# Measurements.net
KiCad netlist of a schematic drawn in Altium Designer
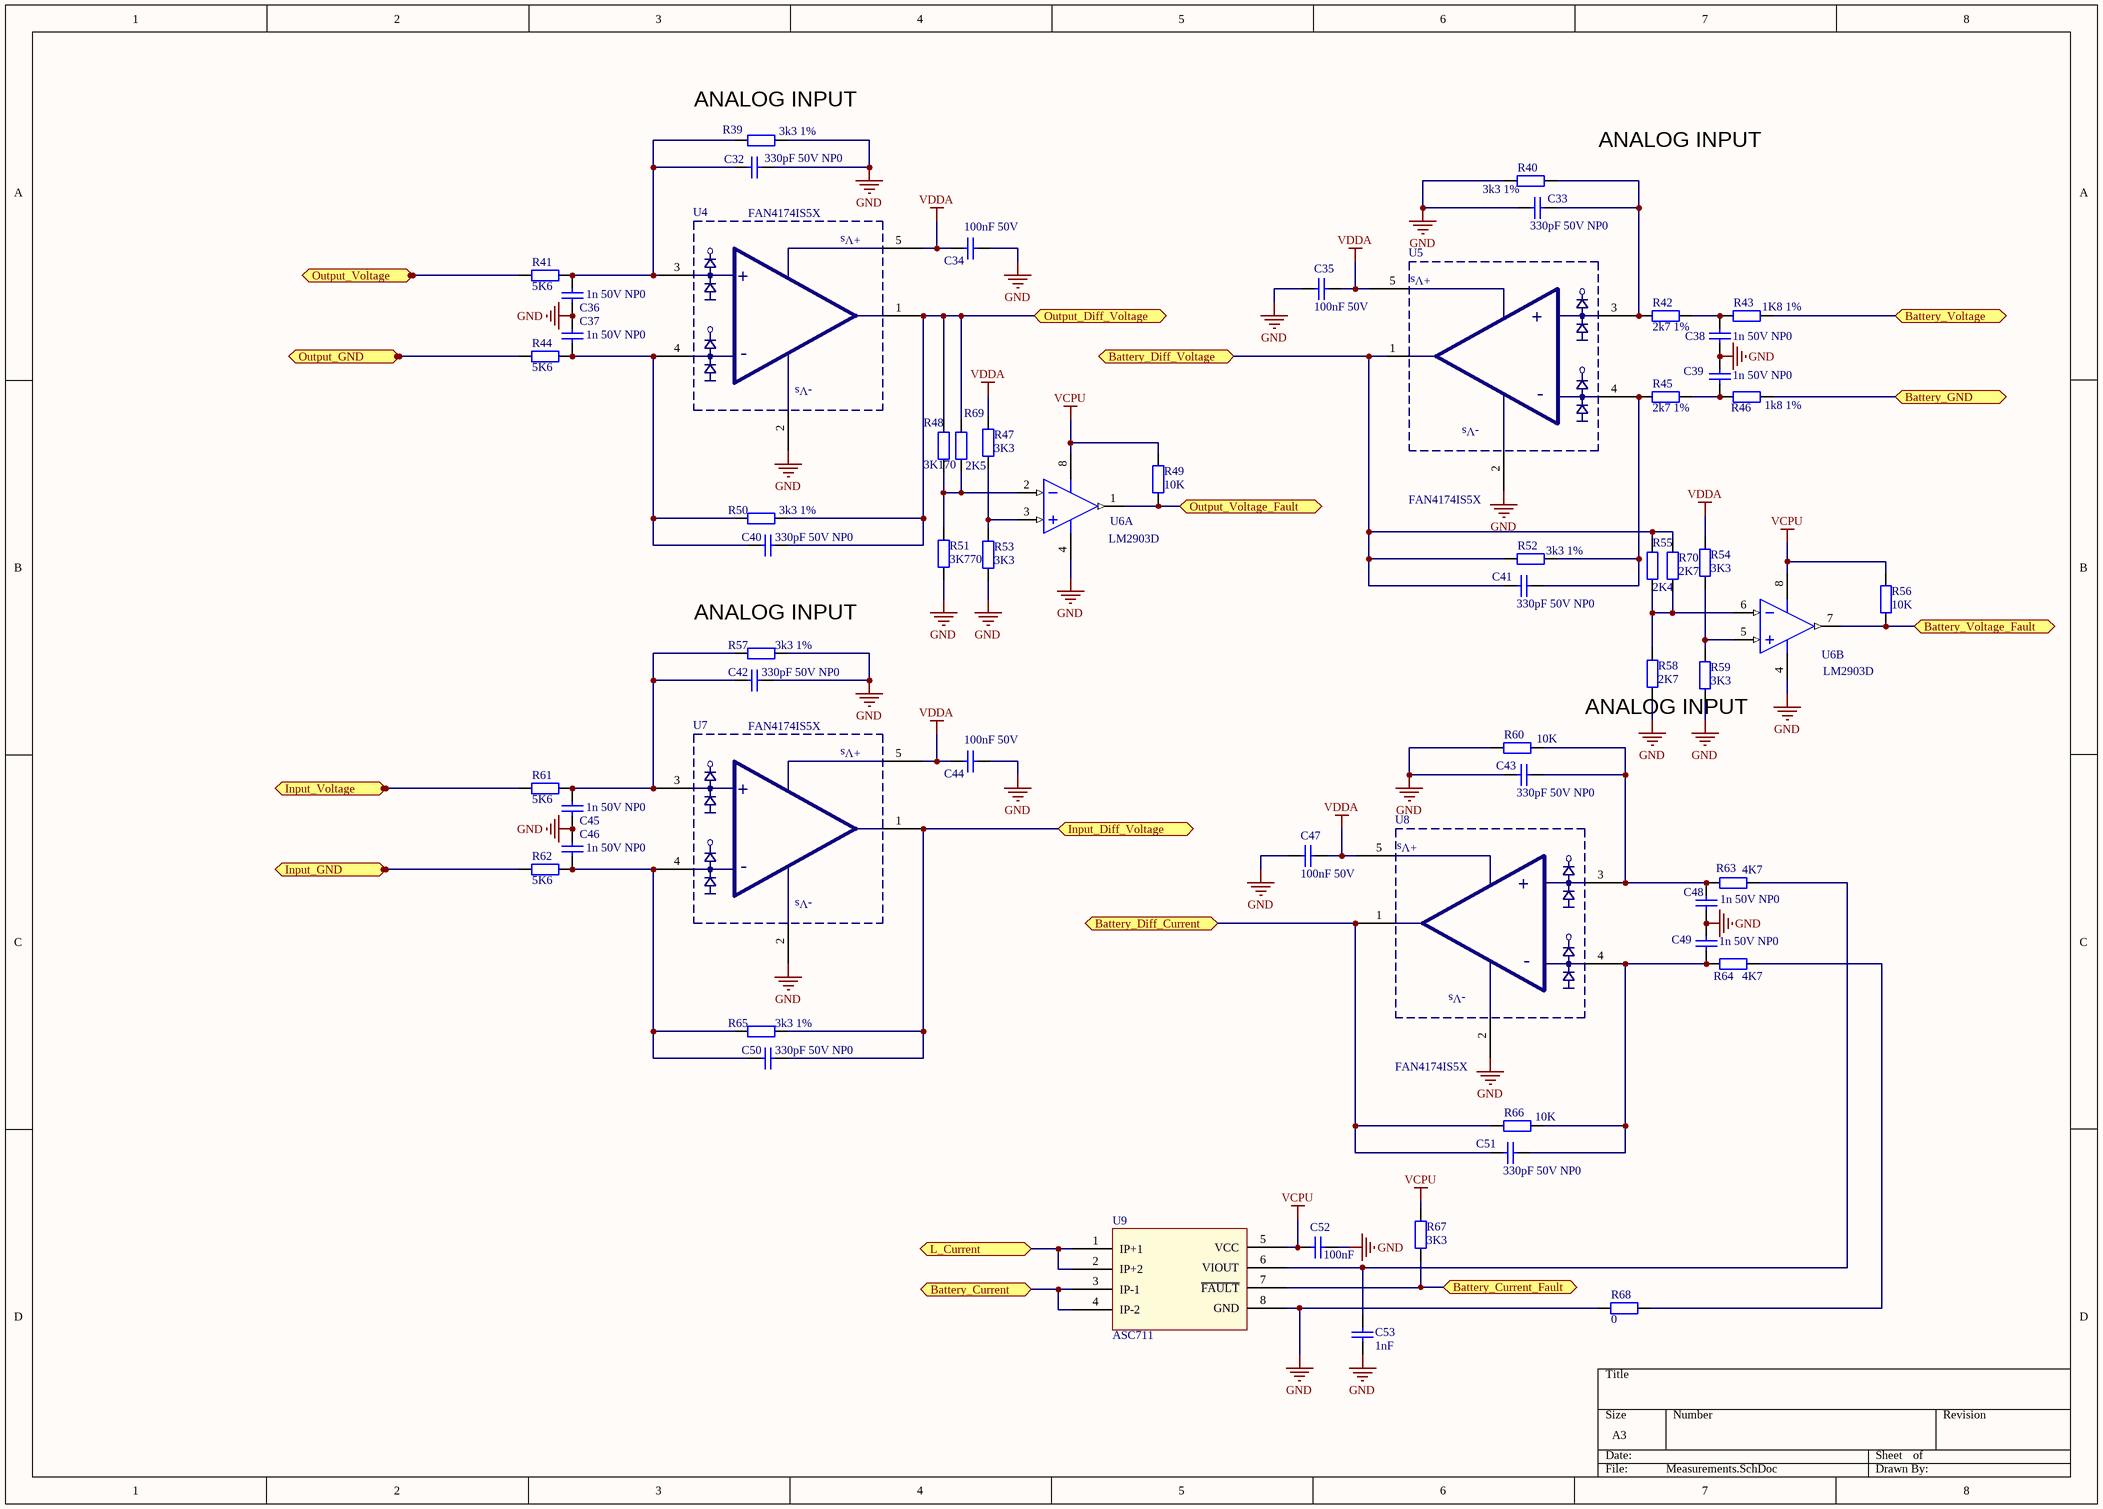
[diagram p0: Measurements.SchDoc]

(export (version "E")
  (design (tool "Eeschema 10.0.6"))
  (components
    (comp (ref "C32")
      (value "330pF 50V NP0")
      (footprint "0805_C")
      (description "SMD kondenzátorok")
      (libsource (lib "MERES") (part "Capacitor_SMD"))
    )
    (comp (ref "C33")
      (value "330pF 50V NP0")
      (footprint "0805_C")
      (description "SMD kondenzátorok")
      (libsource (lib "MERES") (part "Capacitor_SMD"))
    )
    (comp (ref "C34")
      (value "100nF 50V")
      (footprint "0805_C")
      (description "SMD kondenzátorok")
      (libsource (lib "MERES") (part "Capacitor_SMD"))
    )
    (comp (ref "C35")
      (value "100nF 50V")
      (footprint "0805_C")
      (description "SMD kondenzátorok")
      (libsource (lib "MERES") (part "Capacitor_SMD"))
    )
    (comp (ref "C36")
      (value "1n 50V NP0")
      (footprint "FP_0805_CAP_085")
      (libsource (lib "MERES") (part "Capacitor_SMD"))
    )
    (comp (ref "C37")
      (value "1n 50V NP0")
      (footprint "FP_0805_CAP_085")
      (libsource (lib "MERES") (part "Capacitor_SMD"))
    )
    (comp (ref "C38")
      (value "1n 50V NP0")
      (footprint "FP_0805_CAP_085")
      (libsource (lib "MERES") (part "Capacitor_SMD"))
    )
    (comp (ref "C39")
      (value "1n 50V NP0")
      (footprint "FP_0805_CAP_085")
      (libsource (lib "MERES") (part "Capacitor_SMD"))
    )
    (comp (ref "C40")
      (value "330pF 50V NP0")
      (footprint "0805_C")
      (description "SMD kondenzátorok")
      (libsource (lib "MERES") (part "Capacitor_SMD"))
    )
    (comp (ref "C41")
      (value "330pF 50V NP0")
      (footprint "0805_C")
      (description "SMD kondenzátorok")
      (libsource (lib "MERES") (part "Capacitor_SMD"))
    )
    (comp (ref "C42")
      (value "330pF 50V NP0")
      (footprint "0805_C")
      (description "SMD kondenzátorok")
      (libsource (lib "MERES") (part "Capacitor_SMD"))
    )
    (comp (ref "C43")
      (value "330pF 50V NP0")
      (footprint "0805_C")
      (description "SMD kondenzátorok")
      (libsource (lib "MERES") (part "Capacitor_SMD"))
    )
    (comp (ref "C44")
      (value "100nF 50V")
      (footprint "0805_C")
      (description "SMD kondenzátorok")
      (libsource (lib "MERES") (part "Capacitor_SMD"))
    )
    (comp (ref "C45")
      (value "1n 50V NP0")
      (footprint "FP_0805_CAP_085")
      (libsource (lib "MERES") (part "Capacitor_SMD"))
    )
    (comp (ref "C46")
      (value "1n 50V NP0")
      (footprint "FP_0805_CAP_085")
      (libsource (lib "MERES") (part "Capacitor_SMD"))
    )
    (comp (ref "C47")
      (value "100nF 50V")
      (footprint "0805_C")
      (description "SMD kondenzátorok")
      (libsource (lib "MERES") (part "Capacitor_SMD"))
    )
    (comp (ref "C48")
      (value "1n 50V NP0")
      (footprint "FP_0805_CAP_085")
      (libsource (lib "MERES") (part "Capacitor_SMD"))
    )
    (comp (ref "C49")
      (value "1n 50V NP0")
      (footprint "FP_0805_CAP_085")
      (libsource (lib "MERES") (part "Capacitor_SMD"))
    )
    (comp (ref "C50")
      (value "330pF 50V NP0")
      (footprint "0805_C")
      (description "SMD kondenzátorok")
      (libsource (lib "MERES") (part "Capacitor_SMD"))
    )
    (comp (ref "C51")
      (value "330pF 50V NP0")
      (footprint "0805_C")
      (description "SMD kondenzátorok")
      (libsource (lib "MERES") (part "Capacitor_SMD"))
    )
    (comp (ref "C52")
      (value "100nF")
      (footprint "FP_0805_CAP_085")
      (description "Capacitor")
      (libsource (lib "hallglib") (part "CAP"))
    )
    (comp (ref "C53")
      (value "1nF")
      (footprint "FP_0805_CAP_085")
      (description "Capacitor")
      (libsource (lib "hallglib") (part "CAP"))
    )
    (comp (ref "R39")
      (value "3k3 1%")
      (footprint "FP_0805_RES")
      (libsource (lib "hallglib") (part "Resistor"))
    )
    (comp (ref "R40") (value "3k3 1%") (footprint "FP_0805_RES") (libsource (lib "") (part "Resistor_1")))
    (comp (ref "R41")
      (value "5K6")
      (footprint "FP_0805_RES")
      (description "Resistor")
      (libsource (lib "") (part "RES_1"))
    )
    (comp (ref "R42") (value "2k7 1%") (footprint "FP_0805_RES") (libsource (lib "") (part "Resistor_1")))
    (comp (ref "R43") (value "1K8 1%") (footprint "FP_0805_RES") (libsource (lib "") (part "Resistor_1")))
    (comp (ref "R44")
      (value "5K6")
      (footprint "FP_0805_RES")
      (description "Resistor")
      (libsource (lib "") (part "RES_1"))
    )
    (comp (ref "R45") (value "2k7 1%") (footprint "FP_0805_RES") (libsource (lib "") (part "Resistor_1")))
    (comp (ref "R46") (value "1k8 1%") (footprint "FP_0805_RES") (libsource (lib "") (part "Resistor_1")))
    (comp (ref "R47")
      (value "3K3")
      (footprint "FP_0805_RES")
      (description "Resistor")
      (libsource (lib "hallglib") (part "RES"))
    )
    (comp (ref "R48")
      (value "3K170")
      (footprint "FP_0805_RES")
      (description "Resistor")
      (libsource (lib "hallglib") (part "RES"))
    )
    (comp (ref "R49")
      (value "10K")
      (footprint "FP_0805_RES")
      (description "Resistor")
      (libsource (lib "hallglib") (part "RES"))
    )
    (comp (ref "R50")
      (value "3k3 1%")
      (footprint "FP_0805_RES")
      (libsource (lib "hallglib") (part "Resistor"))
    )
    (comp (ref "R51")
      (value "3K770")
      (footprint "FP_0805_RES")
      (description "Resistor")
      (libsource (lib "hallglib") (part "RES"))
    )
    (comp (ref "R52") (value "3k3 1%") (footprint "FP_0805_RES") (libsource (lib "") (part "Resistor_1")))
    (comp (ref "R53")
      (value "3K3")
      (footprint "FP_0805_RES")
      (description "Resistor")
      (libsource (lib "hallglib") (part "RES"))
    )
    (comp (ref "R54")
      (value "3K3")
      (footprint "FP_0805_RES")
      (description "Resistor")
      (libsource (lib "hallglib") (part "RES"))
    )
    (comp (ref "R55")
      (value "2K4")
      (footprint "FP_0805_RES")
      (description "Resistor")
      (libsource (lib "hallglib") (part "RES"))
    )
    (comp (ref "R56")
      (value "10K")
      (footprint "FP_0805_RES")
      (description "Resistor")
      (libsource (lib "hallglib") (part "RES"))
    )
    (comp (ref "R57")
      (value "3k3 1%")
      (footprint "FP_0805_RES")
      (libsource (lib "hallglib") (part "Resistor"))
    )
    (comp (ref "R58")
      (value "2K7")
      (footprint "FP_0805_RES")
      (description "Resistor")
      (libsource (lib "hallglib") (part "RES"))
    )
    (comp (ref "R59")
      (value "3K3")
      (footprint "FP_0805_RES")
      (description "Resistor")
      (libsource (lib "hallglib") (part "RES"))
    )
    (comp (ref "R60") (value "10K") (footprint "FP_0805_RES") (libsource (lib "") (part "Resistor_1")))
    (comp (ref "R61")
      (value "5K6")
      (footprint "FP_0805_RES")
      (description "Resistor")
      (libsource (lib "") (part "RES_1"))
    )
    (comp (ref "R62")
      (value "5K6")
      (footprint "FP_0805_RES")
      (description "Resistor")
      (libsource (lib "") (part "RES_1"))
    )
    (comp (ref "R63")
      (value "4K7")
      (footprint "FP_0805_RES")
      (description "Resistor")
      (libsource (lib "") (part "RES_1"))
    )
    (comp (ref "R64")
      (value "4K7")
      (footprint "FP_0805_RES")
      (description "Resistor")
      (libsource (lib "") (part "RES_1"))
    )
    (comp (ref "R65")
      (value "3k3 1%")
      (footprint "FP_0805_RES")
      (libsource (lib "hallglib") (part "Resistor"))
    )
    (comp (ref "R66") (value "10K") (footprint "FP_0805_RES") (libsource (lib "") (part "Resistor_1")))
    (comp (ref "R67")
      (value "3K3")
      (footprint "FP_0805_RES")
      (description "Resistor")
      (libsource (lib "hallglib") (part "RES"))
    )
    (comp (ref "R68")
      (value "0")
      (footprint "FP_0805_0ohm")
      (description "Resistor")
      (libsource (lib "") (part "RES_1"))
    )
    (comp (ref "R69")
      (value "2K5")
      (footprint "FP_0805_RES")
      (description "Resistor")
      (libsource (lib "hallglib") (part "RES"))
    )
    (comp (ref "R70")
      (value "2K7")
      (footprint "FP_0805_RES")
      (description "Resistor")
      (libsource (lib "hallglib") (part "RES"))
    )
    (comp (ref "U4")
      (value "FAN4174IS5X")
      (footprint "SOT-23-5")
      (libsource (lib "MERES") (part "FAN4174IS5X"))
    )
    (comp (ref "U5")
      (value "FAN4174IS5X")
      (footprint "SOT-23-5")
      (libsource (lib "MERES") (part "FAN4174IS5X"))
    )
    (comp (ref "U6")
      (value "LM2903D")
      (footprint "FP_SO8_MS012AA")
      (description "komparátor")
      (libsource (lib "hallglib") (part "LM2903D"))
    )
    (comp (ref "U7")
      (value "FAN4174IS5X")
      (footprint "SOT-23-5")
      (libsource (lib "MERES") (part "FAN4174IS5X"))
    )
    (comp (ref "U8")
      (value "FAN4174IS5X")
      (footprint "SOT-23-5")
      (libsource (lib "MERES") (part "FAN4174IS5X"))
    )
    (comp (ref "U9")
      (value "ASC711")
      (footprint "SOP8")
      (description "Árammérő")
      (libsource (lib "hallglib") (part "ASC711"))
    )
  )
  (nets
    (net (code "1") (name "/Battery_Current") (class "Default")
      (node (ref "U9") (pin "3") (pinfunction "IP-1_3") (pintype "passive"))
      (node (ref "U9") (pin "4") (pinfunction "IP-2_4") (pintype "passive"))
    )
    (net (code "2") (name "/Battery_Current_Fault") (class "Default")
      (node (ref "R67") (pin "1") (pinfunction "1_1") (pintype "passive"))
      (node (ref "U9") (pin "7") (pinfunction "~{FAULT}_7") (pintype "passive"))
    )
    (net (code "3") (name "/Battery_Diff_Current") (class "Default")
      (node (ref "C51") (pin "2") (pinfunction "2_2") (pintype "passive"))
      (node (ref "R66") (pin "1") (pinfunction "1_1") (pintype "passive"))
      (node (ref "U8") (pin "1") (pinfunction "OUT_1") (pintype "passive"))
    )
    (net (code "4") (name "/Battery_Diff_Voltage") (class "Default")
      (node (ref "C41") (pin "2") (pinfunction "2_2") (pintype "passive"))
      (node (ref "R52") (pin "1") (pinfunction "1_1") (pintype "passive"))
      (node (ref "R55") (pin "2") (pinfunction "2_2") (pintype "passive"))
      (node (ref "R70") (pin "2") (pinfunction "2_2") (pintype "passive"))
      (node (ref "U5") (pin "1") (pinfunction "OUT_1") (pintype "passive"))
    )
    (net (code "5") (name "/Battery_GND") (class "Default")
      (node (ref "R46") (pin "2") (pinfunction "2_2") (pintype "passive"))
    )
    (net (code "6") (name "/Battery_Voltage") (class "Default")
      (node (ref "R43") (pin "2") (pinfunction "2_2") (pintype "passive"))
    )
    (net (code "7") (name "/Battery_Voltage_Fault") (class "Default")
      (node (ref "R56") (pin "1") (pinfunction "1_1") (pintype "passive"))
      (node (ref "U6") (pin "7") (pinfunction "OUT2_7") (pintype "output"))
    )
    (net (code "8") (name "/Input_Diff_Voltage") (class "Default")
      (node (ref "C50") (pin "2") (pinfunction "2_2") (pintype "passive"))
      (node (ref "R65") (pin "1") (pinfunction "1_1") (pintype "passive"))
      (node (ref "U7") (pin "1") (pinfunction "OUT_1") (pintype "passive"))
    )
    (net (code "9") (name "/Input_GND") (class "Default")
      (node (ref "R62") (pin "1") (pinfunction "1_1") (pintype "passive"))
    )
    (net (code "10") (name "/Input_Voltage") (class "Default")
      (node (ref "R61") (pin "1") (pinfunction "1_1") (pintype "passive"))
    )
    (net (code "11") (name "/L_Current") (class "Default")
      (node (ref "U9") (pin "1") (pinfunction "IP+1_1") (pintype "passive"))
      (node (ref "U9") (pin "2") (pinfunction "IP+2_2") (pintype "passive"))
    )
    (net (code "12") (name "/Output_Diff_Voltage") (class "Default")
      (node (ref "C40") (pin "2") (pinfunction "2_2") (pintype "passive"))
      (node (ref "R48") (pin "2") (pinfunction "2_2") (pintype "passive"))
      (node (ref "R50") (pin "1") (pinfunction "1_1") (pintype "passive"))
      (node (ref "R69") (pin "2") (pinfunction "2_2") (pintype "passive"))
      (node (ref "U4") (pin "1") (pinfunction "OUT_1") (pintype "passive"))
    )
    (net (code "13") (name "/Output_GND") (class "Default")
      (node (ref "R44") (pin "1") (pinfunction "1_1") (pintype "passive"))
    )
    (net (code "14") (name "/Output_Voltage") (class "Default")
      (node (ref "R41") (pin "1") (pinfunction "1_1") (pintype "passive"))
    )
    (net (code "15") (name "/Output_Voltage_Fault") (class "Default")
      (node (ref "R49") (pin "1") (pinfunction "1_1") (pintype "passive"))
      (node (ref "U6") (pin "1") (pinfunction "OUT1_1") (pintype "output"))
    )
    (net (code "16") (name "GND") (class "Default")
      (node (ref "C32") (pin "2") (pinfunction "2_2") (pintype "passive"))
      (node (ref "C33") (pin "2") (pinfunction "2_2") (pintype "passive"))
      (node (ref "C34") (pin "1") (pinfunction "1_1") (pintype "passive"))
      (node (ref "C35") (pin "1") (pinfunction "1_1") (pintype "passive"))
      (node (ref "C36") (pin "1") (pinfunction "1_1") (pintype "passive"))
      (node (ref "C37") (pin "2") (pinfunction "2_2") (pintype "passive"))
      (node (ref "C38") (pin "1") (pinfunction "1_1") (pintype "passive"))
      (node (ref "C39") (pin "2") (pinfunction "2_2") (pintype "passive"))
      (node (ref "C42") (pin "2") (pinfunction "2_2") (pintype "passive"))
      (node (ref "C43") (pin "2") (pinfunction "2_2") (pintype "passive"))
      (node (ref "C44") (pin "1") (pinfunction "1_1") (pintype "passive"))
      (node (ref "C45") (pin "1") (pinfunction "1_1") (pintype "passive"))
      (node (ref "C46") (pin "2") (pinfunction "2_2") (pintype "passive"))
      (node (ref "C47") (pin "1") (pinfunction "1_1") (pintype "passive"))
      (node (ref "C48") (pin "1") (pinfunction "1_1") (pintype "passive"))
      (node (ref "C49") (pin "2") (pinfunction "2_2") (pintype "passive"))
      (node (ref "C52") (pin "2") (pinfunction "2_2") (pintype "passive"))
      (node (ref "C53") (pin "1") (pinfunction "1_1") (pintype "passive"))
      (node (ref "R39") (pin "1") (pinfunction "1_1") (pintype "passive"))
      (node (ref "R40") (pin "1") (pinfunction "1_1") (pintype "passive"))
      (node (ref "R51") (pin "1") (pinfunction "1_1") (pintype "passive"))
      (node (ref "R53") (pin "1") (pinfunction "1_1") (pintype "passive"))
      (node (ref "R57") (pin "1") (pinfunction "1_1") (pintype "passive"))
      (node (ref "R58") (pin "1") (pinfunction "1_1") (pintype "passive"))
      (node (ref "R59") (pin "1") (pinfunction "1_1") (pintype "passive"))
      (node (ref "R60") (pin "1") (pinfunction "1_1") (pintype "passive"))
      (node (ref "R68") (pin "1") (pinfunction "1_1") (pintype "passive"))
      (node (ref "U4") (pin "2") (pinfunction "-Vs_2") (pintype "passive"))
      (node (ref "U5") (pin "2") (pinfunction "-Vs_2") (pintype "passive"))
      (node (ref "U6") (pin "4") (pinfunction "GND_4") (pintype "power_in"))
      (node (ref "U7") (pin "2") (pinfunction "-Vs_2") (pintype "passive"))
      (node (ref "U8") (pin "2") (pinfunction "-Vs_2") (pintype "passive"))
      (node (ref "U9") (pin "8") (pinfunction "GND_8") (pintype "passive"))
    )
    (net (code "17") (name "Net-(C38-Pad2)") (class "Default")
      (node (ref "C38") (pin "2") (pinfunction "2_2") (pintype "passive"))
      (node (ref "R42") (pin "2") (pinfunction "2_2") (pintype "passive"))
      (node (ref "R43") (pin "1") (pinfunction "1_1") (pintype "passive"))
    )
    (net (code "18") (name "Net-(C39-Pad1)") (class "Default")
      (node (ref "C39") (pin "1") (pinfunction "1_1") (pintype "passive"))
      (node (ref "R45") (pin "2") (pinfunction "2_2") (pintype "passive"))
      (node (ref "R46") (pin "1") (pinfunction "1_1") (pintype "passive"))
    )
    (net (code "19") (name "Net-(R64-Pad2)") (class "Default")
      (node (ref "R64") (pin "2") (pinfunction "2_2") (pintype "passive"))
      (node (ref "R68") (pin "2") (pinfunction "2_2") (pintype "passive"))
    )
    (net (code "20") (name "Net-(U4-+IN)") (class "Default")
      (node (ref "C32") (pin "1") (pinfunction "1_1") (pintype "passive"))
      (node (ref "C36") (pin "2") (pinfunction "2_2") (pintype "passive"))
      (node (ref "R39") (pin "2") (pinfunction "2_2") (pintype "passive"))
      (node (ref "R41") (pin "2") (pinfunction "2_2") (pintype "passive"))
      (node (ref "U4") (pin "3") (pinfunction "+IN_3") (pintype "passive"))
    )
    (net (code "21") (name "Net-(U4--IN)") (class "Default")
      (node (ref "C37") (pin "1") (pinfunction "1_1") (pintype "passive"))
      (node (ref "C40") (pin "1") (pinfunction "1_1") (pintype "passive"))
      (node (ref "R44") (pin "2") (pinfunction "2_2") (pintype "passive"))
      (node (ref "R50") (pin "2") (pinfunction "2_2") (pintype "passive"))
      (node (ref "U4") (pin "4") (pinfunction "-IN_4") (pintype "passive"))
    )
    (net (code "22") (name "Net-(U5-+IN)") (class "Default")
      (node (ref "C33") (pin "1") (pinfunction "1_1") (pintype "passive"))
      (node (ref "R40") (pin "2") (pinfunction "2_2") (pintype "passive"))
      (node (ref "R42") (pin "1") (pinfunction "1_1") (pintype "passive"))
      (node (ref "U5") (pin "3") (pinfunction "+IN_3") (pintype "passive"))
    )
    (net (code "23") (name "Net-(U5--IN)") (class "Default")
      (node (ref "C41") (pin "1") (pinfunction "1_1") (pintype "passive"))
      (node (ref "R45") (pin "1") (pinfunction "1_1") (pintype "passive"))
      (node (ref "R52") (pin "2") (pinfunction "2_2") (pintype "passive"))
      (node (ref "U5") (pin "4") (pinfunction "-IN_4") (pintype "passive"))
    )
    (net (code "24") (name "Net-(U6A-IN1+)") (class "Default")
      (node (ref "R47") (pin "1") (pinfunction "1_1") (pintype "passive"))
      (node (ref "R53") (pin "2") (pinfunction "2_2") (pintype "passive"))
      (node (ref "U6") (pin "3") (pinfunction "IN1+_3") (pintype "input"))
    )
    (net (code "25") (name "Net-(U6A-IN1-)") (class "Default")
      (node (ref "R48") (pin "1") (pinfunction "1_1") (pintype "passive"))
      (node (ref "R51") (pin "2") (pinfunction "2_2") (pintype "passive"))
      (node (ref "R69") (pin "1") (pinfunction "1_1") (pintype "passive"))
      (node (ref "U6") (pin "2") (pinfunction "IN1-_2") (pintype "input"))
    )
    (net (code "26") (name "Net-(U6B-IN2+)") (class "Default")
      (node (ref "R54") (pin "1") (pinfunction "1_1") (pintype "passive"))
      (node (ref "R59") (pin "2") (pinfunction "2_2") (pintype "passive"))
      (node (ref "U6") (pin "5") (pinfunction "IN2+_5") (pintype "input"))
    )
    (net (code "27") (name "Net-(U6B-IN2-)") (class "Default")
      (node (ref "R55") (pin "1") (pinfunction "1_1") (pintype "passive"))
      (node (ref "R58") (pin "2") (pinfunction "2_2") (pintype "passive"))
      (node (ref "R70") (pin "1") (pinfunction "1_1") (pintype "passive"))
      (node (ref "U6") (pin "6") (pinfunction "IN2-_6") (pintype "input"))
    )
    (net (code "28") (name "Net-(U7-+IN)") (class "Default")
      (node (ref "C42") (pin "1") (pinfunction "1_1") (pintype "passive"))
      (node (ref "C45") (pin "2") (pinfunction "2_2") (pintype "passive"))
      (node (ref "R57") (pin "2") (pinfunction "2_2") (pintype "passive"))
      (node (ref "R61") (pin "2") (pinfunction "2_2") (pintype "passive"))
      (node (ref "U7") (pin "3") (pinfunction "+IN_3") (pintype "passive"))
    )
    (net (code "29") (name "Net-(U7--IN)") (class "Default")
      (node (ref "C46") (pin "1") (pinfunction "1_1") (pintype "passive"))
      (node (ref "C50") (pin "1") (pinfunction "1_1") (pintype "passive"))
      (node (ref "R62") (pin "2") (pinfunction "2_2") (pintype "passive"))
      (node (ref "R65") (pin "2") (pinfunction "2_2") (pintype "passive"))
      (node (ref "U7") (pin "4") (pinfunction "-IN_4") (pintype "passive"))
    )
    (net (code "30") (name "Net-(U8-+IN)") (class "Default")
      (node (ref "C43") (pin "1") (pinfunction "1_1") (pintype "passive"))
      (node (ref "C48") (pin "2") (pinfunction "2_2") (pintype "passive"))
      (node (ref "R60") (pin "2") (pinfunction "2_2") (pintype "passive"))
      (node (ref "R63") (pin "1") (pinfunction "1_1") (pintype "passive"))
      (node (ref "U8") (pin "3") (pinfunction "+IN_3") (pintype "passive"))
    )
    (net (code "31") (name "Net-(U8--IN)") (class "Default")
      (node (ref "C49") (pin "1") (pinfunction "1_1") (pintype "passive"))
      (node (ref "C51") (pin "1") (pinfunction "1_1") (pintype "passive"))
      (node (ref "R64") (pin "1") (pinfunction "1_1") (pintype "passive"))
      (node (ref "R66") (pin "2") (pinfunction "2_2") (pintype "passive"))
      (node (ref "U8") (pin "4") (pinfunction "-IN_4") (pintype "passive"))
    )
    (net (code "32") (name "Net-(U9-VIOUT)") (class "Default")
      (node (ref "C53") (pin "2") (pinfunction "2_2") (pintype "passive"))
      (node (ref "R63") (pin "2") (pinfunction "2_2") (pintype "passive"))
      (node (ref "U9") (pin "6") (pinfunction "VIOUT_6") (pintype "passive"))
    )
    (net (code "33") (name "VCPU") (class "Default")
      (node (ref "C52") (pin "1") (pinfunction "1_1") (pintype "passive"))
      (node (ref "R49") (pin "2") (pinfunction "2_2") (pintype "passive"))
      (node (ref "R56") (pin "2") (pinfunction "2_2") (pintype "passive"))
      (node (ref "R67") (pin "2") (pinfunction "2_2") (pintype "passive"))
      (node (ref "U6") (pin "8") (pinfunction "VCC_8") (pintype "power_in"))
      (node (ref "U9") (pin "5") (pinfunction "VCC_5") (pintype "passive"))
    )
    (net (code "34") (name "VDDA") (class "Default")
      (node (ref "C34") (pin "2") (pinfunction "2_2") (pintype "passive"))
      (node (ref "C35") (pin "2") (pinfunction "2_2") (pintype "passive"))
      (node (ref "C44") (pin "2") (pinfunction "2_2") (pintype "passive"))
      (node (ref "C47") (pin "2") (pinfunction "2_2") (pintype "passive"))
      (node (ref "R47") (pin "2") (pinfunction "2_2") (pintype "passive"))
      (node (ref "R54") (pin "2") (pinfunction "2_2") (pintype "passive"))
      (node (ref "U4") (pin "5") (pinfunction "+Vs_5") (pintype "passive"))
      (node (ref "U5") (pin "5") (pinfunction "+Vs_5") (pintype "passive"))
      (node (ref "U7") (pin "5") (pinfunction "+Vs_5") (pintype "passive"))
      (node (ref "U8") (pin "5") (pinfunction "+Vs_5") (pintype "passive"))
    )
  )
)
